# power.net
KiCad netlist of a schematic drawn in Altium Designer
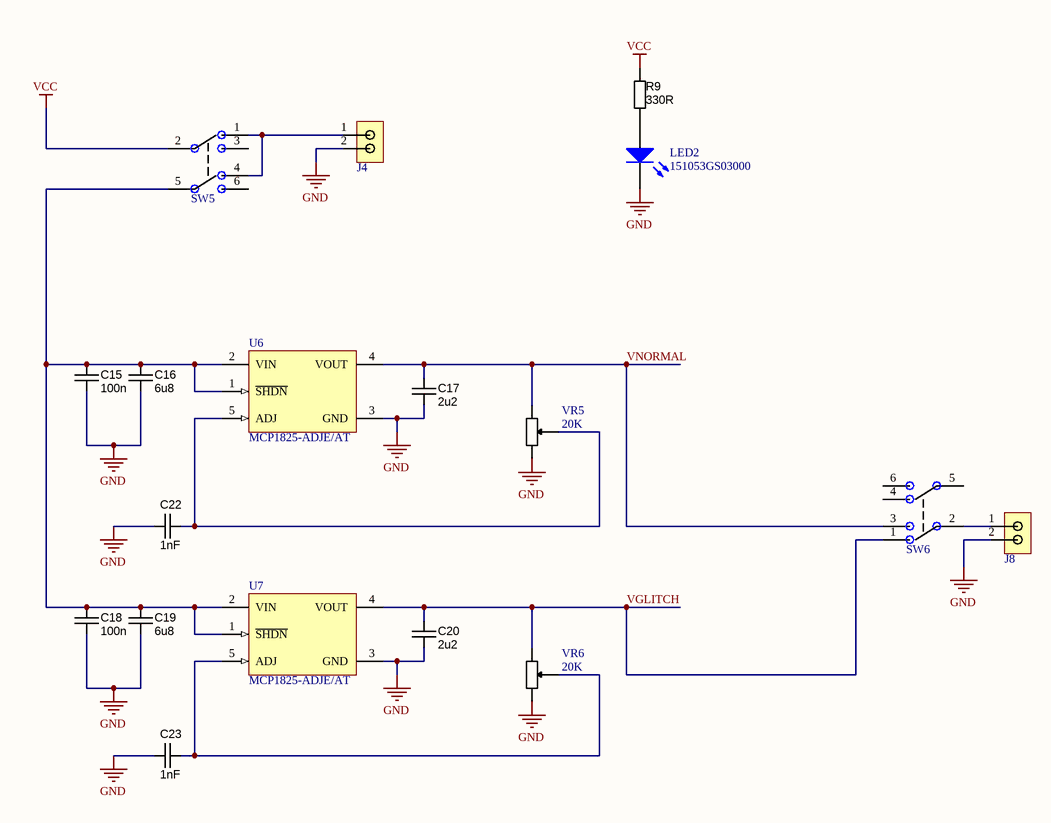
[diagram p0: power.SchDoc]

(export (version "E")
  (design (tool "Eeschema 10.0.6"))
  (components
    (comp (ref "C15")
      (value "100n")
      (footprint "CAPC500P450250X550")
      (description "Capacitor Ceramic 220nF 10% 50V X7R radial 5mm lead spacing")
      (fields (field (name "TOLERANCE") "±10%") (field (name "Comment") "approved sub OK"))
      (libsource (lib "PBL - Capacitors") (part "CAPR_220n_Radial_5mm"))
    )
    (comp (ref "C16")
      (value "6u8")
      (footprint "CAPC500P450250X550")
      (description "Capacitor Ceramic 220nF 10% 50V X7R radial 5mm lead spacing")
      (fields (field (name "TOLERANCE") "±10%") (field (name "Comment") "approved sub OK"))
      (libsource (lib "PBL - Capacitors") (part "CAPR_220n_Radial_5mm"))
    )
    (comp (ref "C17")
      (value "2u2")
      (footprint "CAPC500P450250X550")
      (description "Capacitor Ceramic 220nF 10% 50V X7R radial 5mm lead spacing")
      (fields (field (name "TOLERANCE") "±10%") (field (name "Comment") "approved sub OK"))
      (libsource (lib "PBL - Capacitors") (part "CAPR_220n_Radial_5mm"))
    )
    (comp (ref "C18")
      (value "100n")
      (footprint "CAPC500P450250X550")
      (description "Capacitor Ceramic 220nF 10% 50V X7R radial 5mm lead spacing")
      (fields (field (name "TOLERANCE") "±10%") (field (name "Comment") "approved sub OK"))
      (libsource (lib "PBL - Capacitors") (part "CAPR_220n_Radial_5mm"))
    )
    (comp (ref "C19")
      (value "6u8")
      (footprint "CAPC500P450250X550")
      (description "Capacitor Ceramic 220nF 10% 50V X7R radial 5mm lead spacing")
      (fields (field (name "TOLERANCE") "±10%") (field (name "Comment") "approved sub OK"))
      (libsource (lib "PBL - Capacitors") (part "CAPR_220n_Radial_5mm"))
    )
    (comp (ref "C20")
      (value "2u2")
      (footprint "CAPC500P450250X550")
      (description "Capacitor Ceramic 220nF 10% 50V X7R radial 5mm lead spacing")
      (fields (field (name "TOLERANCE") "±10%") (field (name "Comment") "approved sub OK"))
      (libsource (lib "PBL - Capacitors") (part "CAPR_220n_Radial_5mm"))
    )
    (comp (ref "C22")
      (value "1nF")
      (footprint "CAPC500P450250X550")
      (description "Capacitor Ceramic 220nF 10% 50V X7R radial 5mm lead spacing")
      (fields (field (name "TOLERANCE") "±10%") (field (name "Comment") "approved sub OK"))
      (libsource (lib "PBL - Capacitors") (part "CAPR_220n_Radial_5mm"))
    )
    (comp (ref "C23")
      (value "1nF")
      (footprint "CAPC500P450250X550")
      (description "Capacitor Ceramic 220nF 10% 50V X7R radial 5mm lead spacing")
      (fields (field (name "TOLERANCE") "±10%") (field (name "Comment") "approved sub OK"))
      (libsource (lib "PBL - Capacitors") (part "CAPR_220n_Radial_5mm"))
    )
    (comp (ref "J4")
      (value "Jumper")
      (footprint "2x2.54mm_Header")
      (description "1x2 2.54mm header, male pins")
      (fields (field (name "PART NUMBER") "2_PIN_JUMPER"))
      (libsource (lib "NewAE_AltiumLib") (part "1x2_Pin_Header"))
    )
    (comp (ref "J8")
      (value "Jumper")
      (footprint "2x2.54mm_Header")
      (description "1x2 2.54mm header, male pins")
      (fields (field (name "PART NUMBER") "2_PIN_JUMPER"))
      (libsource (lib "NewAE_AltiumLib") (part "1x2_Pin_Header"))
    )
    (comp (ref "LED2")
      (value "151053GS03000")
      (footprint "Type 5mm")
      (description "THT LED round mono-color waterclear, WL-TMRW, Green")
      (fields (field (name "MANUFACTURER") "Wuerth Elektronik"))
      (libsource (lib "Altium Content Vault") (part "WE-LED_K1A2-2"))
    )
    (comp (ref "R9")
      (value "330R")
      (footprint "RESTH_AXIAL-0.4")
      (description "Resistor THD Axial 10K Ohm 0.25W 5% Carbon Film")
      (fields (field (name "TOLERANCE") "±5%") (field (name "Comment") "Carbon Film"))
      (libsource (lib "PBL - Resistors") (part "RES_220R_Axial_0.25W_5%"))
    )
    (comp (ref "SW5")
      (value "EG2207")
      (footprint "EG2207")
      (description "DPDT Switch with 2 MH")
      (libsource (lib "NewAE_AltiumLib") (part "SW_DPDT_2MH"))
    )
    (comp (ref "SW6")
      (value "EG2207")
      (footprint "EG2207")
      (description "DPDT Switch with 2 MH")
      (libsource (lib "NewAE_AltiumLib") (part "SW_DPDT_2MH"))
    )
    (comp (ref "U6")
      (value "MCP1825-ADJE/AT")
      (footprint "TO-220-AT5")
      (description "500 mA, Low Voltage, Low Quiescent Current LDO Regulator, 5-Pin TO-220, Extended Temperature")
      (libsource (lib "Altium Content Vault") (part "PM-LINEREG-MCP1825-IL5A"))
    )
    (comp (ref "U7")
      (value "MCP1825-ADJE/AT")
      (footprint "TO-220-AT5")
      (description "500 mA, Low Voltage, Low Quiescent Current LDO Regulator, 5-Pin TO-220, Extended Temperature")
      (libsource (lib "Altium Content Vault") (part "PM-LINEREG-MCP1825-IL5A"))
    )
    (comp (ref "VR5")
      (value "20K")
      (footprint "RES_PDB18")
      (description "POT 1/5W CARBON LINEAR VAR RESISTOR")
      (fields (field (name "PART NUMBER") "POT_PDB181"))
      (libsource (lib "NewAE_AltiumLib") (part "Potentiometer"))
    )
    (comp (ref "VR6")
      (value "20K")
      (footprint "RES_PDB18")
      (description "POT 1/5W CARBON LINEAR VAR RESISTOR")
      (fields (field (name "PART NUMBER") "POT_PDB181"))
      (libsource (lib "NewAE_AltiumLib") (part "Potentiometer"))
    )
  )
  (nets
    (net (code "1") (name "/VGLITCH") (class "Default")
      (node (ref "C20") (pin "2") (pintype "passive"))
      (node (ref "SW6") (pin "1") (pinfunction "IN_1") (pintype "passive"))
      (node (ref "U7") (pin "4") (pinfunction "VOUT_4") (pintype "power_in"))
      (node (ref "VR6") (pin "1") (pinfunction "1_1") (pintype "passive"))
    )
    (net (code "2") (name "/VNORMAL") (class "Default")
      (node (ref "C17") (pin "2") (pintype "passive"))
      (node (ref "SW6") (pin "3") (pinfunction "IN_3") (pintype "passive"))
      (node (ref "U6") (pin "4") (pinfunction "VOUT_4") (pintype "power_in"))
      (node (ref "VR5") (pin "1") (pinfunction "1_1") (pintype "passive"))
    )
    (net (code "3") (name "GND") (class "Default")
      (node (ref "C15") (pin "1") (pintype "passive"))
      (node (ref "C16") (pin "1") (pintype "passive"))
      (node (ref "C17") (pin "1") (pintype "passive"))
      (node (ref "C18") (pin "1") (pintype "passive"))
      (node (ref "C19") (pin "1") (pintype "passive"))
      (node (ref "C20") (pin "1") (pintype "passive"))
      (node (ref "C22") (pin "2") (pintype "passive"))
      (node (ref "C23") (pin "2") (pintype "passive"))
      (node (ref "J4") (pin "2") (pinfunction "2_2") (pintype "passive"))
      (node (ref "J8") (pin "2") (pinfunction "2_2") (pintype "passive"))
      (node (ref "LED2") (pin "1") (pinfunction "K_1") (pintype "passive"))
      (node (ref "U6") (pin "3") (pinfunction "GND_3") (pintype "power_in"))
      (node (ref "U7") (pin "3") (pinfunction "GND_3") (pintype "power_in"))
      (node (ref "VR5") (pin "3") (pinfunction "3_3") (pintype "passive"))
      (node (ref "VR6") (pin "3") (pinfunction "3_3") (pintype "passive"))
    )
    (net (code "4") (name "Net-(J4-Pad1)") (class "Default")
      (node (ref "J4") (pin "1") (pinfunction "1_1") (pintype "passive"))
      (node (ref "SW5") (pin "1") (pinfunction "IN_1") (pintype "passive"))
      (node (ref "SW5") (pin "4") (pinfunction "IN_4") (pintype "passive"))
    )
    (net (code "5") (name "Net-(J8-Pad1)") (class "Default")
      (node (ref "J8") (pin "1") (pinfunction "1_1") (pintype "passive"))
      (node (ref "SW6") (pin "2") (pinfunction "IN_2") (pintype "passive"))
    )
    (net (code "6") (name "Net-(LED2-A)") (class "Default")
      (node (ref "LED2") (pin "2") (pinfunction "A_2") (pintype "passive"))
      (node (ref "R9") (pin "2") (pinfunction "2_2") (pintype "passive"))
    )
    (net (code "7") (name "Net-(U6-ADJ)") (class "Default")
      (node (ref "C22") (pin "1") (pintype "passive"))
      (node (ref "U6") (pin "5") (pinfunction "ADJ_5") (pintype "input"))
      (node (ref "VR5") (pin "2") (pinfunction "2_2") (pintype "passive"))
    )
    (net (code "8") (name "Net-(U6-VIN)") (class "Default")
      (node (ref "C15") (pin "2") (pintype "passive"))
      (node (ref "C16") (pin "2") (pintype "passive"))
      (node (ref "C18") (pin "2") (pintype "passive"))
      (node (ref "C19") (pin "2") (pintype "passive"))
      (node (ref "SW5") (pin "5") (pinfunction "IN_5") (pintype "passive"))
      (node (ref "U6") (pin "1") (pinfunction "~{SHDN}_1") (pintype "input"))
      (node (ref "U6") (pin "2") (pinfunction "VIN_2") (pintype "power_in"))
      (node (ref "U7") (pin "1") (pinfunction "~{SHDN}_1") (pintype "input"))
      (node (ref "U7") (pin "2") (pinfunction "VIN_2") (pintype "power_in"))
    )
    (net (code "9") (name "Net-(U7-ADJ)") (class "Default")
      (node (ref "C23") (pin "1") (pintype "passive"))
      (node (ref "U7") (pin "5") (pinfunction "ADJ_5") (pintype "input"))
      (node (ref "VR6") (pin "2") (pinfunction "2_2") (pintype "passive"))
    )
    (net (code "10") (name "VCC") (class "Default")
      (node (ref "R9") (pin "1") (pinfunction "1_1") (pintype "passive"))
      (node (ref "SW5") (pin "2") (pinfunction "IN_2") (pintype "passive"))
    )
    (net (code "11") (name "unconnected-(SW5-IN-Pad3)") (class "Default")
      (node (ref "SW5") (pin "3") (pinfunction "IN_3") (pintype "passive"))
    )
    (net (code "12") (name "unconnected-(SW5-IN-Pad6)") (class "Default")
      (node (ref "SW5") (pin "6") (pinfunction "IN_6") (pintype "passive"))
    )
    (net (code "13") (name "unconnected-(SW6-IN-Pad4)") (class "Default")
      (node (ref "SW6") (pin "4") (pinfunction "IN_4") (pintype "passive"))
    )
    (net (code "14") (name "unconnected-(SW6-IN-Pad5)") (class "Default")
      (node (ref "SW6") (pin "5") (pinfunction "IN_5") (pintype "passive"))
    )
    (net (code "15") (name "unconnected-(SW6-IN-Pad6)") (class "Default")
      (node (ref "SW6") (pin "6") (pinfunction "IN_6") (pintype "passive"))
    )
  )
)
